# USB.net
KiCad netlist of a schematic drawn in Altium Designer
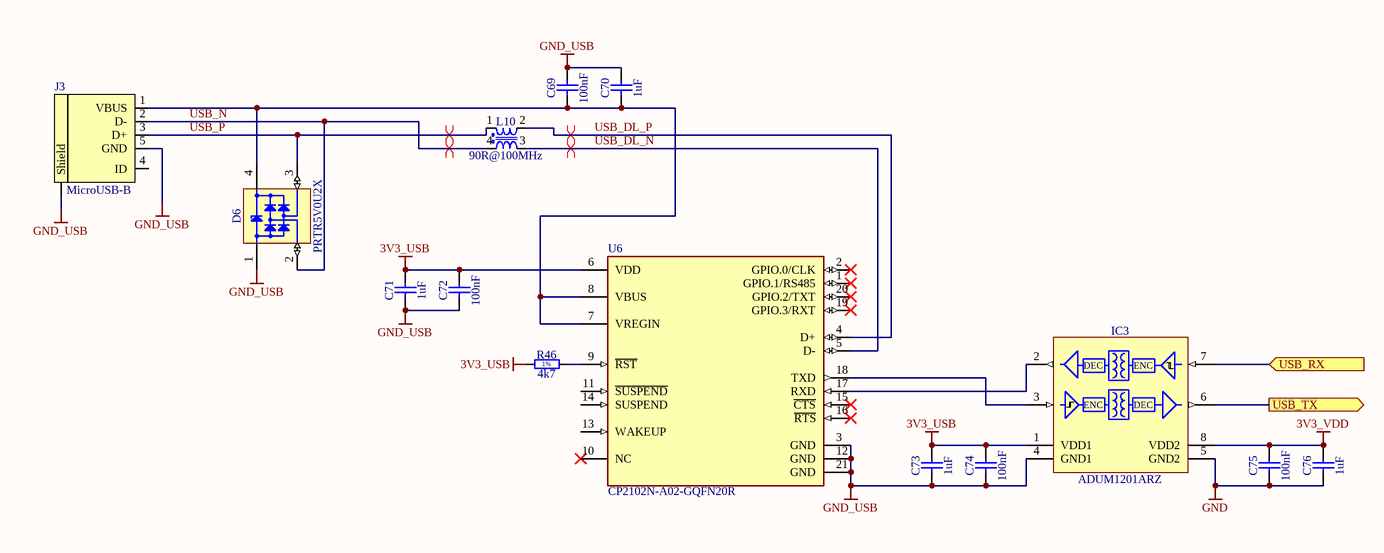
[diagram p0: USB.SchDoc]

(export (version "E")
  (design (tool "Eeschema 10.0.6"))
  (components
    (comp (ref "C69")
      (value "100nF")
      (footprint "CAPC1005X55N")
      (description "Non-polarised capacitor")
      (fields
        (field (name "PART NUMBER") "CC0402_100NF_16V_10%_X5R")
        (field (name "VOLTAGE") "16V")
        (field (name "AUTHOR") "CERN DEM JLC")
      )
      (libsource (lib "Capacitors") (part "Capacitor - non polarized"))
    )
    (comp (ref "C70")
      (value "1uF")
      (footprint "CAPC1005X55N")
      (description "Non-polarised capacitor")
      (fields
        (field (name "PART NUMBER") "CC0402_1UF_16V_10%_X5R")
        (field (name "VOLTAGE") "16V")
        (field (name "AUTHOR") "CERN DEM JLC")
      )
      (libsource (lib "Capacitors") (part "Capacitor - non polarized"))
    )
    (comp (ref "C71")
      (value "1uF")
      (footprint "CAPC1005X55N")
      (description "Non-polarised capacitor")
      (fields
        (field (name "PART NUMBER") "CC0402_1UF_16V_10%_X5R")
        (field (name "VOLTAGE") "16V")
        (field (name "AUTHOR") "CERN DEM JLC")
      )
      (libsource (lib "Capacitors") (part "Capacitor - non polarized"))
    )
    (comp (ref "C72")
      (value "100nF")
      (footprint "CAPC1005X55N")
      (description "Non-polarised capacitor")
      (fields
        (field (name "PART NUMBER") "CC0402_100NF_16V_10%_X5R")
        (field (name "VOLTAGE") "16V")
        (field (name "AUTHOR") "CERN DEM JLC")
      )
      (libsource (lib "Capacitors") (part "Capacitor - non polarized"))
    )
    (comp (ref "C73")
      (value "1uF")
      (footprint "CAPC1005X55N")
      (description "Non-polarised capacitor")
      (fields
        (field (name "PART NUMBER") "CC0402_1UF_16V_10%_X5R")
        (field (name "VOLTAGE") "16V")
        (field (name "AUTHOR") "CERN DEM JLC")
      )
      (libsource (lib "Capacitors") (part "Capacitor - non polarized"))
    )
    (comp (ref "C74")
      (value "100nF")
      (footprint "CAPC1005X55N")
      (description "Non-polarised capacitor")
      (fields
        (field (name "PART NUMBER") "CC0402_100NF_16V_10%_X5R")
        (field (name "VOLTAGE") "16V")
        (field (name "AUTHOR") "CERN DEM JLC")
      )
      (libsource (lib "Capacitors") (part "Capacitor - non polarized"))
    )
    (comp (ref "C75")
      (value "100nF")
      (footprint "CAPC1005X55N")
      (description "Non-polarised capacitor")
      (fields
        (field (name "PART NUMBER") "CC0402_100NF_16V_10%_X5R")
        (field (name "VOLTAGE") "16V")
        (field (name "AUTHOR") "CERN DEM JLC")
      )
      (libsource (lib "Capacitors") (part "Capacitor - non polarized"))
    )
    (comp (ref "C76")
      (value "1uF")
      (footprint "CAPC1005X55N")
      (description "Non-polarised capacitor")
      (fields
        (field (name "PART NUMBER") "CC0402_1UF_16V_10%_X5R")
        (field (name "VOLTAGE") "16V")
        (field (name "AUTHOR") "CERN DEM JLC")
      )
      (libsource (lib "Capacitors") (part "Capacitor - non polarized"))
    )
    (comp (ref "D6")
      (value "PRTR5V0U2X")
      (footprint "SOT190P230X110-4N")
      (description "Ultra Low Capacitance Double Rail-to-Rail ESD Protection Diode")
      (fields
        (field (name "VOLTAGE") "5.5V")
        (field (name "MANUFACTURER") "NXP SEMICONDUCTORS")
        (field (name "AUTHOR") "CERN DEM JLC")
      )
      (libsource (lib "ICs And Semiconductors") (part "PRTR5V0U2X"))
    )
    (comp (ref "IC3")
      (value "ADUM1201ARZ")
      (footprint "SOIC127P600X175-8N")
      (description "Dual-Channel Digital Isolators")
      (fields (field (name "MANUFACTURER") "ANALOG DEVICES") (field (name "AUTHOR") "CERN DEM BC"))
      (libsource (lib "ICs And Semiconductors") (part "ADUM1201"))
    )
    (comp (ref "J3")
      (value "MicroUSB-B")
      (footprint "USB-Micro-B-RA-SMD-PiP")
      (description "MicroUSB-B-SMT")
      (fields
        (field (name "PART NUMBER") "USB-Micro-B-RA-SMD-PiP")
        (field (name "MANUFACTURER") "Allen Creations Corp.")
        (field (name "PUBLISHER") "Nordic Semiconductor")
      )
      (libsource (lib "pca10028") (part "MiniUSB-AB-SMT"))
    )
    (comp (ref "L10")
      (value "90R@100MHz")
      (footprint "IND_MURATA_DLW21S")
      (description "Inductor Common Mode")
      (fields
        (field (name "PART NUMBER") "IND_MURATA_DLW21SN900SQ2L")
        (field (name "POWER") "330mA")
        (field (name "AUTHOR") "CERN DEM JLC")
      )
      (libsource (lib "Inductors & Transformers") (part "Inductor Common Mode 1Dot-2 4Dot-3"))
    )
    (comp (ref "R46")
      (value "4k7")
      (footprint "RESC1005X40N")
      (description "Resistor - 1%")
      (fields
        (field (name "PART NUMBER") "R0402_4K7_1%_0.0625W_100PPM")
        (field (name "POWER") "0.0625W")
        (field (name "AUTHOR") "CERN DEM JLC")
      )
      (libsource (lib "Resistors") (part "Resistor - 1%"))
    )
    (comp (ref "U6")
      (value "CP2102N-A02-GQFN20R")
      (footprint "FP-CP2102N-A02-GQFN20R-MFG")
      (description "IC USB TO UART BRIDGE QFN20")
      (libsource (lib "Altium Content Vault") (part "12297b18919ed2bc2a0fed00377f037"))
    )
  )
  (nets
    (net (code "1") (name "/USB_DL_N") (class "Default")
      (node (ref "L10") (pin "3") (pinfunction "3_3") (pintype "passive"))
      (node (ref "U6") (pin "5") (pinfunction "D-_5") (pintype "bidirectional"))
    )
    (net (code "2") (name "/USB_DL_P") (class "Default")
      (node (ref "L10") (pin "2") (pinfunction "2_2") (pintype "passive"))
      (node (ref "U6") (pin "4") (pinfunction "D+_4") (pintype "bidirectional"))
    )
    (net (code "3") (name "/USB_N") (class "Default")
      (node (ref "D6") (pin "2") (pinfunction "I/O1_2") (pintype "bidirectional"))
      (node (ref "J3") (pin "2") (pinfunction "D-_2") (pintype "passive"))
      (node (ref "L10") (pin "4") (pinfunction "4_4") (pintype "passive"))
    )
    (net (code "4") (name "/USB_P") (class "Default")
      (node (ref "D6") (pin "3") (pinfunction "I/O2_3") (pintype "bidirectional"))
      (node (ref "J3") (pin "3") (pinfunction "D+_3") (pintype "passive"))
      (node (ref "L10") (pin "1") (pinfunction "1_1") (pintype "passive"))
    )
    (net (code "5") (name "/USB_RX") (class "Default")
      (node (ref "IC3") (pin "7") (pinfunction "VIA_7") (pintype "input"))
    )
    (net (code "6") (name "/USB_TX") (class "Default")
      (node (ref "IC3") (pin "6") (pinfunction "VOB_6") (pintype "output"))
    )
    (net (code "7") (name "3V3_USB") (class "Default")
      (node (ref "C71") (pin "2") (pinfunction "2_2") (pintype "passive"))
      (node (ref "C72") (pin "2") (pinfunction "2_2") (pintype "passive"))
      (node (ref "C73") (pin "2") (pinfunction "2_2") (pintype "passive"))
      (node (ref "C74") (pin "2") (pinfunction "2_2") (pintype "passive"))
      (node (ref "IC3") (pin "1") (pinfunction "VDD1_1") (pintype "power_in"))
      (node (ref "R46") (pin "1") (pinfunction "1_1") (pintype "passive"))
      (node (ref "U6") (pin "6") (pinfunction "VDD_6") (pintype "power_in"))
    )
    (net (code "8") (name "3V3_VDD") (class "Default")
      (node (ref "C75") (pin "2") (pinfunction "2_2") (pintype "passive"))
      (node (ref "C76") (pin "2") (pinfunction "2_2") (pintype "passive"))
      (node (ref "IC3") (pin "8") (pinfunction "VDD2_8") (pintype "power_in"))
    )
    (net (code "9") (name "GND") (class "Default")
      (node (ref "C75") (pin "1") (pinfunction "1_1") (pintype "passive"))
      (node (ref "C76") (pin "1") (pinfunction "1_1") (pintype "passive"))
      (node (ref "IC3") (pin "5") (pinfunction "GND2_5") (pintype "power_in"))
    )
    (net (code "10") (name "GND_USB") (class "Default")
      (node (ref "C69") (pin "2") (pinfunction "2_2") (pintype "passive"))
      (node (ref "C70") (pin "2") (pinfunction "2_2") (pintype "passive"))
      (node (ref "C71") (pin "1") (pinfunction "1_1") (pintype "passive"))
      (node (ref "C72") (pin "1") (pinfunction "1_1") (pintype "passive"))
      (node (ref "C73") (pin "1") (pinfunction "1_1") (pintype "passive"))
      (node (ref "C74") (pin "1") (pinfunction "1_1") (pintype "passive"))
      (node (ref "D6") (pin "1") (pinfunction "GND_1") (pintype "power_in"))
      (node (ref "IC3") (pin "4") (pinfunction "GND1_4") (pintype "power_in"))
      (node (ref "J3") (pin "5") (pinfunction "GND_5") (pintype "power_in"))
      (node (ref "J3") (pin "6") (pinfunction "Shield_6") (pintype "power_in"))
      (node (ref "U6") (pin "12") (pinfunction "GND_12") (pintype "power_in"))
      (node (ref "U6") (pin "21") (pinfunction "GND_21") (pintype "power_in"))
      (node (ref "U6") (pin "3") (pinfunction "GND_3") (pintype "power_in"))
    )
    (net (code "11") (name "Net-(D6-VCC)") (class "Default")
      (node (ref "C69") (pin "1") (pinfunction "1_1") (pintype "passive"))
      (node (ref "C70") (pin "1") (pinfunction "1_1") (pintype "passive"))
      (node (ref "D6") (pin "4") (pinfunction "VCC_4") (pintype "power_in"))
      (node (ref "J3") (pin "1") (pinfunction "VBUS_1") (pintype "power_in"))
      (node (ref "U6") (pin "7") (pinfunction "VREGIN_7") (pintype "passive"))
      (node (ref "U6") (pin "8") (pinfunction "VBUS_8") (pintype "power_in"))
    )
    (net (code "12") (name "Net-(IC3-VIB)") (class "Default")
      (node (ref "IC3") (pin "3") (pinfunction "VIB_3") (pintype "input"))
      (node (ref "U6") (pin "18") (pinfunction "TXD_18") (pintype "output"))
    )
    (net (code "13") (name "Net-(IC3-VOA)") (class "Default")
      (node (ref "IC3") (pin "2") (pinfunction "VOA_2") (pintype "output"))
      (node (ref "U6") (pin "17") (pinfunction "RXD_17") (pintype "input"))
    )
    (net (code "14") (name "Net-(U6-~{RST})") (class "Default")
      (node (ref "R46") (pin "2") (pinfunction "2_2") (pintype "passive"))
      (node (ref "U6") (pin "9") (pinfunction "~{RST}_9") (pintype "input"))
    )
    (net (code "15") (name "unconnected-(J3-ID-Pad4)") (class "Default")
      (node (ref "J3") (pin "4") (pinfunction "ID_4") (pintype "passive"))
    )
    (net (code "16") (name "unconnected-(U6-GPIO.0{slash}CLK-Pad2)") (class "Default")
      (node (ref "U6") (pin "2") (pinfunction "GPIO.0/CLK_2") (pintype "bidirectional+no_connect"))
    )
    (net (code "17") (name "unconnected-(U6-GPIO.1{slash}RS485-Pad1)") (class "Default")
      (node (ref "U6") (pin "1") (pinfunction "GPIO.1/RS485_1") (pintype "bidirectional+no_connect"))
    )
    (net (code "18") (name "unconnected-(U6-GPIO.2{slash}TXT-Pad20)") (class "Default")
      (node (ref "U6") (pin "20") (pinfunction "GPIO.2/TXT_20") (pintype "bidirectional+no_connect"))
    )
    (net (code "19") (name "unconnected-(U6-GPIO.3{slash}RXT-Pad19)") (class "Default")
      (node (ref "U6") (pin "19") (pinfunction "GPIO.3/RXT_19") (pintype "bidirectional+no_connect"))
    )
    (net (code "20") (name "unconnected-(U6-NC-Pad10)") (class "Default")
      (node (ref "U6") (pin "10") (pinfunction "NC_10") (pintype "passive+no_connect"))
    )
    (net (code "21") (name "unconnected-(U6-SUSPEND-Pad14)") (class "Default")
      (node (ref "U6") (pin "14") (pinfunction "SUSPEND_14") (pintype "input"))
    )
    (net (code "22") (name "unconnected-(U6-WAKEUP-Pad13)") (class "Default")
      (node (ref "U6") (pin "13") (pinfunction "WAKEUP_13") (pintype "input"))
    )
    (net (code "23") (name "unconnected-(U6-~{CTS}-Pad15)") (class "Default")
      (node (ref "U6") (pin "15") (pinfunction "~{CTS}_15") (pintype "input+no_connect"))
    )
    (net (code "24") (name "unconnected-(U6-~{RTS}-Pad16)") (class "Default")
      (node (ref "U6") (pin "16") (pinfunction "~{RTS}_16") (pintype "input+no_connect"))
    )
    (net (code "25") (name "unconnected-(U6-~{SUSPEND}-Pad11)") (class "Default")
      (node (ref "U6") (pin "11") (pinfunction "~{SUSPEND}_11") (pintype "input"))
    )
  )
)
